# SCH_Radio.net
KiCad netlist of a schematic drawn in Altium Designer
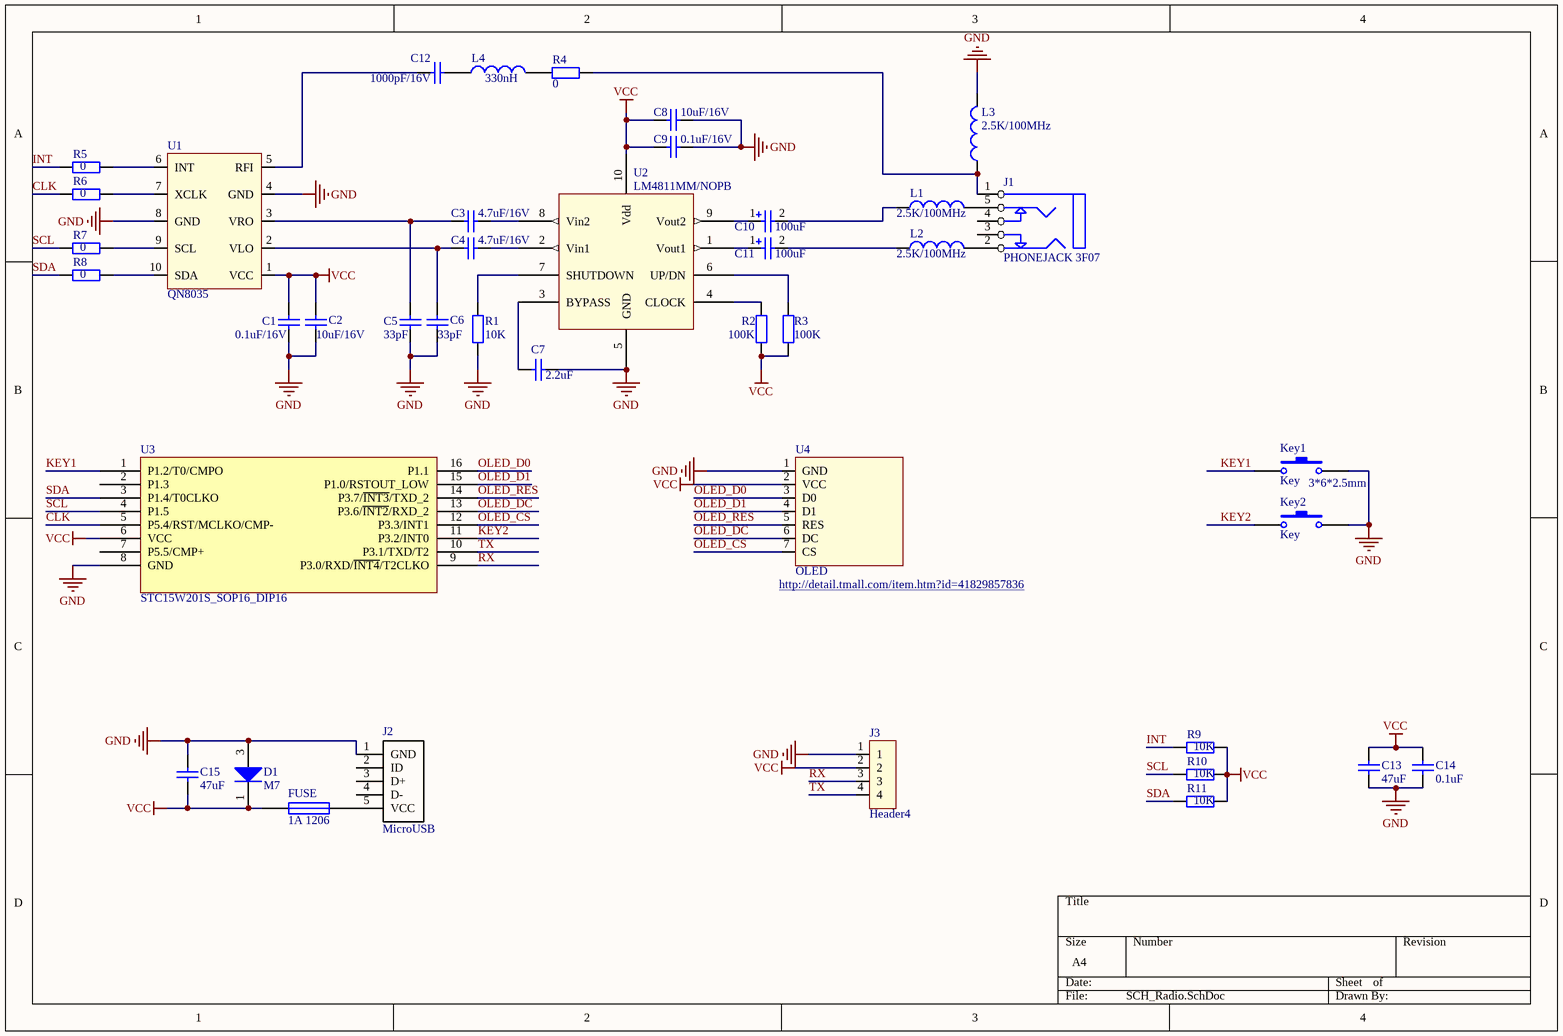
[diagram p0: SCH_Radio.SchDoc]

(export (version "E")
  (design (tool "Eeschema 10.0.6"))
  (components
    (comp (ref "C1")
      (value "0.1uF/16V")
      (footprint "0603")
      (description "Capacitor")
      (fields (field (name "Comment") "Cap") (field (name "PUBLISHER") "Altium Limited"))
      (libsource (lib "Miscellaneous Devices") (part "Cap"))
    )
    (comp (ref "C2")
      (value "10uF/16V")
      (footprint "0805")
      (description "Capacitor")
      (fields (field (name "Comment") "Cap") (field (name "PUBLISHER") "Altium Limited"))
      (libsource (lib "Miscellaneous Devices") (part "Cap"))
    )
    (comp (ref "C3")
      (value "4.7uF/16V")
      (footprint "0603")
      (description "Capacitor")
      (fields (field (name "Comment") "Cap") (field (name "PUBLISHER") "Altium Limited"))
      (libsource (lib "Miscellaneous Devices") (part "Cap"))
    )
    (comp (ref "C4")
      (value "4.7uF/16V")
      (footprint "0603")
      (description "Capacitor")
      (fields (field (name "Comment") "Cap") (field (name "PUBLISHER") "Altium Limited"))
      (libsource (lib "Miscellaneous Devices") (part "Cap"))
    )
    (comp (ref "C5")
      (value "33pF")
      (footprint "0603")
      (description "Capacitor")
      (fields (field (name "Comment") "Cap") (field (name "PUBLISHER") "Altium Limited"))
      (libsource (lib "Miscellaneous Devices") (part "Cap"))
    )
    (comp (ref "C6")
      (value "33pF")
      (footprint "0603")
      (description "Capacitor")
      (fields (field (name "Comment") "Cap") (field (name "PUBLISHER") "Altium Limited"))
      (libsource (lib "Miscellaneous Devices") (part "Cap"))
    )
    (comp (ref "C7")
      (value "2.2uF")
      (footprint "0603")
      (description "Capacitor")
      (fields (field (name "Comment") "Cap") (field (name "PUBLISHER") "Altium Limited"))
      (libsource (lib "Miscellaneous Devices") (part "Cap"))
    )
    (comp (ref "C8")
      (value "10uF/16V")
      (footprint "0805")
      (description "Capacitor")
      (fields (field (name "Comment") "Cap") (field (name "PUBLISHER") "Altium Limited"))
      (libsource (lib "Miscellaneous Devices") (part "Cap"))
    )
    (comp (ref "C9")
      (value "0.1uF/16V")
      (footprint "0603")
      (description "Capacitor")
      (fields (field (name "Comment") "Cap") (field (name "PUBLISHER") "Altium Limited"))
      (libsource (lib "Miscellaneous Devices") (part "Cap"))
    )
    (comp (ref "C10")
      (value "100uF")
      (footprint "6032")
      (description "Polarized Capacitor (Axial)")
      (fields (field (name "Comment") "Cap Pol2") (field (name "PUBLISHER") "Altium Limited"))
      (libsource (lib "Miscellaneous Devices") (part "Cap Pol2"))
    )
    (comp (ref "C11")
      (value "100uF")
      (footprint "6032")
      (description "Polarized Capacitor (Axial)")
      (fields (field (name "Comment") "Cap Pol2") (field (name "PUBLISHER") "Altium Limited"))
      (libsource (lib "Miscellaneous Devices") (part "Cap Pol2"))
    )
    (comp (ref "C12")
      (value "1000pF/16V")
      (footprint "0603")
      (description "Capacitor")
      (fields (field (name "Comment") "Cap") (field (name "PUBLISHER") "Altium Limited"))
      (libsource (lib "Miscellaneous Devices") (part "Cap"))
    )
    (comp (ref "C13")
      (value "47uF")
      (footprint "0805")
      (description "Capacitor")
      (fields (field (name "Comment") "Cap") (field (name "PUBLISHER") "Altium Limited"))
      (libsource (lib "Miscellaneous Devices") (part "Cap"))
    )
    (comp (ref "C14")
      (value "0.1uF")
      (footprint "0603")
      (description "Capacitor")
      (fields (field (name "Comment") "Cap") (field (name "PUBLISHER") "Altium Limited"))
      (libsource (lib "Miscellaneous Devices") (part "Cap"))
    )
    (comp (ref "C15")
      (value "47uF")
      (footprint "0805")
      (description "Capacitor")
      (fields (field (name "Comment") "Cap") (field (name "PUBLISHER") "Altium Limited"))
      (libsource (lib "Miscellaneous Devices") (part "Cap"))
    )
    (comp (ref "D1")
      (value "M7")
      (footprint "DO-214AC")
      (description "Default Diode")
      (fields (field (name "PUBLISHER") "Altium Limited"))
      (libsource (lib "Miscellaneous Devices") (part "Diode"))
    )
    (comp (ref "FUSE")
      (value "1A 1206")
      (footprint "1206")
      (description "Fuse")
      (fields (field (name "PUBLISHER") "Altium Limited"))
      (libsource (lib "Miscellaneous Devices") (part "Fuse 1"))
    )
    (comp (ref "J1")
      (value "PHONEJACK 3F07")
      (footprint "3F07")
      (libsource (lib "SCH_Library") (part "PHONEJACK STEREO SW"))
    )
    (comp (ref "J2")
      (value "MicroUSB")
      (footprint "MicroUSB")
      (description "Imported")
      (libsource (lib "SCH_Library") (part "MicroUSB"))
    )
    (comp (ref "J3") (value "Header4") (footprint "HEADER4") (libsource (lib "SCH_Library") (part "Header4")))
    (comp (ref "Key1")
      (value "Key")
      (footprint "key")
      (fields (field (name "G") "3*6*2.5mm"))
      (libsource (lib "SCH_Library") (part "Key"))
    )
    (comp (ref "Key2") (value "Key") (footprint "key") (libsource (lib "SCH_Library") (part "Key")))
    (comp (ref "L1")
      (value "2.5K/100MHz")
      (footprint "0603")
      (description "Inductor")
      (fields (field (name "PUBLISHER") "Altium Limited"))
      (libsource (lib "Miscellaneous Devices") (part "Inductor"))
    )
    (comp (ref "L2")
      (value "2.5K/100MHz")
      (footprint "0603")
      (description "Inductor")
      (fields (field (name "PUBLISHER") "Altium Limited"))
      (libsource (lib "Miscellaneous Devices") (part "Inductor"))
    )
    (comp (ref "L3")
      (value "2.5K/100MHz")
      (footprint "0603")
      (description "Inductor")
      (fields (field (name "PUBLISHER") "Altium Limited"))
      (libsource (lib "Miscellaneous Devices") (part "Inductor"))
    )
    (comp (ref "L4")
      (value "330nH")
      (footprint "0603")
      (description "Inductor")
      (fields (field (name "PUBLISHER") "Altium Limited"))
      (libsource (lib "Miscellaneous Devices") (part "Inductor"))
    )
    (comp (ref "R1")
      (value "10K")
      (footprint "0603")
      (description "Resistor")
      (fields (field (name "Comment") "Res2") (field (name "PUBLISHER") "Altium Limited"))
      (libsource (lib "Miscellaneous Devices") (part "Res2"))
    )
    (comp (ref "R2")
      (value "100K")
      (footprint "0603")
      (description "Resistor")
      (fields (field (name "Comment") "Res2") (field (name "PUBLISHER") "Altium Limited"))
      (libsource (lib "Miscellaneous Devices") (part "Res2"))
    )
    (comp (ref "R3")
      (value "100K")
      (footprint "0603")
      (description "Resistor")
      (fields (field (name "Comment") "Res2") (field (name "PUBLISHER") "Altium Limited"))
      (libsource (lib "Miscellaneous Devices") (part "Res2"))
    )
    (comp (ref "R4")
      (value "0")
      (footprint "0603")
      (description "Resistor")
      (fields (field (name "Comment") "Res2") (field (name "PUBLISHER") "Altium Limited"))
      (libsource (lib "") (part "Res2_1"))
    )
    (comp (ref "R5")
      (value "0")
      (footprint "0603")
      (description "Resistor")
      (fields (field (name "Comment") "Res2") (field (name "PUBLISHER") "Altium Limited"))
      (libsource (lib "") (part "Res2_1"))
    )
    (comp (ref "R6")
      (value "0")
      (footprint "0603")
      (description "Resistor")
      (fields (field (name "Comment") "Res2") (field (name "PUBLISHER") "Altium Limited"))
      (libsource (lib "") (part "Res2_1"))
    )
    (comp (ref "R7")
      (value "0")
      (footprint "0603")
      (description "Resistor")
      (fields (field (name "Comment") "Res2") (field (name "PUBLISHER") "Altium Limited"))
      (libsource (lib "") (part "Res2_1"))
    )
    (comp (ref "R8")
      (value "0")
      (footprint "0603")
      (description "Resistor")
      (fields (field (name "Comment") "Res2") (field (name "PUBLISHER") "Altium Limited"))
      (libsource (lib "") (part "Res2_1"))
    )
    (comp (ref "R9")
      (value "10K")
      (footprint "0603")
      (description "Resistor")
      (fields (field (name "Comment") "Res2") (field (name "PUBLISHER") "Altium Limited"))
      (libsource (lib "") (part "Res2_1"))
    )
    (comp (ref "R10")
      (value "10K")
      (footprint "0603")
      (description "Resistor")
      (fields (field (name "Comment") "Res2") (field (name "PUBLISHER") "Altium Limited"))
      (libsource (lib "") (part "Res2_1"))
    )
    (comp (ref "R11")
      (value "10K")
      (footprint "0603")
      (description "Resistor")
      (fields (field (name "Comment") "Res2") (field (name "PUBLISHER") "Altium Limited"))
      (libsource (lib "") (part "Res2_1"))
    )
    (comp (ref "U1") (value "QN8035") (footprint "SOP10") (libsource (lib "SCH_Library") (part "QN8035")))
    (comp (ref "U2")
      (value "LM4811MM/NOPB")
      (footprint "MUB10Am")
      (description "Imported")
      (fields (field (name "RS PART NUMBER") "5359802"))
      (libsource (lib "SCH_Library") (part "LM4811MM/NOPB"))
    )
    (comp (ref "U3")
      (value "STC15W201S_SOP16_DIP16")
      (footprint "SOP16")
      (libsource (lib "SCH_Library") (part "STC15W201S_SOP16_DIP16"))
    )
    (comp (ref "U4")
      (value "OLED")
      (footprint "OLED_0.96")
      (fields (field (name "URL") "http://detail.tmall.com/item.htm?id=41829857836"))
      (libsource (lib "SCH_Library") (part "OLED"))
    )
  )
  (nets
    (net (code "1") (name "/CLK") (class "Default")
      (node (ref "R6") (pin "2") (pinfunction "2_2") (pintype "passive"))
      (node (ref "U3") (pin "5") (pinfunction "P5.4/RST/MCLKO/CMP-_5") (pintype "passive"))
    )
    (net (code "2") (name "/INT") (class "Default")
      (node (ref "R5") (pin "2") (pinfunction "2_2") (pintype "passive"))
      (node (ref "R9") (pin "2") (pinfunction "2_2") (pintype "passive"))
    )
    (net (code "3") (name "/KEY1") (class "Default")
      (node (ref "Key1") (pin "1") (pinfunction "1_1") (pintype "passive"))
      (node (ref "U3") (pin "1") (pinfunction "P1.2/T0/CMPO_1") (pintype "passive"))
    )
    (net (code "4") (name "/KEY2") (class "Default")
      (node (ref "Key2") (pin "1") (pinfunction "1_1") (pintype "passive"))
      (node (ref "U3") (pin "11") (pinfunction "P3.2/INT0_11") (pintype "passive"))
    )
    (net (code "5") (name "/OLED_CS") (class "Default")
      (node (ref "U3") (pin "12") (pinfunction "P3.3/INT1_12") (pintype "passive"))
      (node (ref "U4") (pin "7") (pinfunction "CS_7") (pintype "passive"))
    )
    (net (code "6") (name "/OLED_D0") (class "Default")
      (node (ref "U3") (pin "16") (pinfunction "P1.1_16") (pintype "passive"))
      (node (ref "U4") (pin "3") (pinfunction "D0_3") (pintype "passive"))
    )
    (net (code "7") (name "/OLED_D1") (class "Default")
      (node (ref "U3") (pin "15") (pinfunction "P1.0/RSTOUT_LOW_15") (pintype "passive"))
      (node (ref "U4") (pin "4") (pinfunction "D1_4") (pintype "passive"))
    )
    (net (code "8") (name "/OLED_DC") (class "Default")
      (node (ref "U3") (pin "13") (pinfunction "P3.6/~{INT2}/RXD_2_13") (pintype "passive"))
      (node (ref "U4") (pin "6") (pinfunction "DC_6") (pintype "passive"))
    )
    (net (code "9") (name "/OLED_RES") (class "Default")
      (node (ref "U3") (pin "14") (pinfunction "P3.7/~{INT3}/TXD_2_14") (pintype "passive"))
      (node (ref "U4") (pin "5") (pinfunction "RES_5") (pintype "passive"))
    )
    (net (code "10") (name "/RX") (class "Default")
      (node (ref "J3") (pin "3") (pinfunction "3_3") (pintype "passive"))
      (node (ref "U3") (pin "9") (pinfunction "P3.0/RXD/~{INT4}/T2CLKO_9") (pintype "passive"))
    )
    (net (code "11") (name "/SCL") (class "Default")
      (node (ref "R10") (pin "2") (pinfunction "2_2") (pintype "passive"))
      (node (ref "R7") (pin "2") (pinfunction "2_2") (pintype "passive"))
      (node (ref "U3") (pin "4") (pinfunction "P1.5_4") (pintype "passive"))
    )
    (net (code "12") (name "/SDA") (class "Default")
      (node (ref "R11") (pin "2") (pinfunction "2_2") (pintype "passive"))
      (node (ref "R8") (pin "2") (pinfunction "2_2") (pintype "passive"))
      (node (ref "U3") (pin "3") (pinfunction "P1.4/T0CLKO_3") (pintype "passive"))
    )
    (net (code "13") (name "/TX") (class "Default")
      (node (ref "J3") (pin "4") (pinfunction "4_4") (pintype "passive"))
      (node (ref "U3") (pin "10") (pinfunction "P3.1/TXD/T2_10") (pintype "passive"))
    )
    (net (code "14") (name "GND") (class "Default")
      (node (ref "C1") (pin "1") (pinfunction "1_1") (pintype "passive"))
      (node (ref "C13") (pin "2") (pinfunction "2_2") (pintype "passive"))
      (node (ref "C14") (pin "2") (pinfunction "2_2") (pintype "passive"))
      (node (ref "C15") (pin "1") (pinfunction "1_1") (pintype "passive"))
      (node (ref "C2") (pin "1") (pinfunction "1_1") (pintype "passive"))
      (node (ref "C5") (pin "1") (pinfunction "1_1") (pintype "passive"))
      (node (ref "C6") (pin "1") (pinfunction "1_1") (pintype "passive"))
      (node (ref "C7") (pin "2") (pinfunction "2_2") (pintype "passive"))
      (node (ref "C8") (pin "2") (pinfunction "2_2") (pintype "passive"))
      (node (ref "C9") (pin "2") (pinfunction "2_2") (pintype "passive"))
      (node (ref "D1") (pin "3") (pinfunction "A_3") (pintype "passive"))
      (node (ref "J2") (pin "1") (pinfunction "GND_1") (pintype "passive"))
      (node (ref "J3") (pin "1") (pinfunction "1_1") (pintype "passive"))
      (node (ref "Key1") (pin "2") (pinfunction "2_2") (pintype "passive"))
      (node (ref "Key2") (pin "2") (pinfunction "2_2") (pintype "passive"))
      (node (ref "L3") (pin "2") (pinfunction "2_2") (pintype "passive"))
      (node (ref "R1") (pin "1") (pinfunction "1_1") (pintype "passive"))
      (node (ref "U1") (pin "4") (pinfunction "GND_4") (pintype "passive"))
      (node (ref "U1") (pin "8") (pinfunction "GND_8") (pintype "passive"))
      (node (ref "U2") (pin "5") (pinfunction "GND_5") (pintype "passive"))
      (node (ref "U3") (pin "8") (pinfunction "GND_8") (pintype "passive"))
      (node (ref "U4") (pin "1") (pinfunction "GND_1") (pintype "passive"))
    )
    (net (code "15") (name "Net-(C10-Pad2)") (class "Default")
      (node (ref "C10") (pin "2") (pinfunction "2_2") (pintype "passive"))
      (node (ref "L1") (pin "1") (pinfunction "1_1") (pintype "passive"))
    )
    (net (code "16") (name "Net-(C11-Pad2)") (class "Default")
      (node (ref "C11") (pin "2") (pinfunction "2_2") (pintype "passive"))
      (node (ref "L2") (pin "1") (pinfunction "1_1") (pintype "passive"))
    )
    (net (code "17") (name "Net-(C12-Pad1)") (class "Default")
      (node (ref "C12") (pin "1") (pinfunction "1_1") (pintype "passive"))
      (node (ref "L4") (pin "1") (pinfunction "1_1") (pintype "passive"))
    )
    (net (code "18") (name "Net-(J1-A)") (class "Default")
      (node (ref "J1") (pin "2") (pinfunction "A_2") (pintype "passive"))
      (node (ref "L2") (pin "2") (pinfunction "2_2") (pintype "passive"))
    )
    (net (code "19") (name "Net-(J1-D)") (class "Default")
      (node (ref "J1") (pin "5") (pinfunction "D_5") (pintype "passive"))
      (node (ref "L1") (pin "2") (pinfunction "2_2") (pintype "passive"))
    )
    (net (code "20") (name "Net-(J1-E)") (class "Default")
      (node (ref "J1") (pin "1") (pinfunction "E_1") (pintype "passive"))
      (node (ref "L3") (pin "1") (pinfunction "1_1") (pintype "passive"))
      (node (ref "R4") (pin "1") (pinfunction "1_1") (pintype "passive"))
    )
    (net (code "21") (name "Net-(J2-VCC)") (class "Default")
      (node (ref "FUSE") (pin "2") (pinfunction "2_2") (pintype "passive"))
      (node (ref "J2") (pin "5") (pinfunction "VCC_5") (pintype "passive"))
    )
    (net (code "22") (name "Net-(L4-Pad2)") (class "Default")
      (node (ref "L4") (pin "2") (pinfunction "2_2") (pintype "passive"))
      (node (ref "R4") (pin "2") (pinfunction "2_2") (pintype "passive"))
    )
    (net (code "23") (name "Net-(U1-INT)") (class "Default")
      (node (ref "R5") (pin "1") (pinfunction "1_1") (pintype "passive"))
      (node (ref "U1") (pin "6") (pinfunction "INT_6") (pintype "passive"))
    )
    (net (code "24") (name "Net-(U1-RFI)") (class "Default")
      (node (ref "C12") (pin "2") (pinfunction "2_2") (pintype "passive"))
      (node (ref "U1") (pin "5") (pinfunction "RFI_5") (pintype "passive"))
    )
    (net (code "25") (name "Net-(U1-SCL)") (class "Default")
      (node (ref "R7") (pin "1") (pinfunction "1_1") (pintype "passive"))
      (node (ref "U1") (pin "9") (pinfunction "SCL_9") (pintype "passive"))
    )
    (net (code "26") (name "Net-(U1-SDA)") (class "Default")
      (node (ref "R8") (pin "1") (pinfunction "1_1") (pintype "passive"))
      (node (ref "U1") (pin "10") (pinfunction "SDA_10") (pintype "passive"))
    )
    (net (code "27") (name "Net-(U1-VLO)") (class "Default")
      (node (ref "C4") (pin "1") (pinfunction "1_1") (pintype "passive"))
      (node (ref "C6") (pin "2") (pinfunction "2_2") (pintype "passive"))
      (node (ref "U1") (pin "2") (pinfunction "VLO_2") (pintype "passive"))
    )
    (net (code "28") (name "Net-(U1-VRO)") (class "Default")
      (node (ref "C3") (pin "1") (pinfunction "1_1") (pintype "passive"))
      (node (ref "C5") (pin "2") (pinfunction "2_2") (pintype "passive"))
      (node (ref "U1") (pin "3") (pinfunction "VRO_3") (pintype "passive"))
    )
    (net (code "29") (name "Net-(U1-XCLK)") (class "Default")
      (node (ref "R6") (pin "1") (pinfunction "1_1") (pintype "passive"))
      (node (ref "U1") (pin "7") (pinfunction "XCLK_7") (pintype "passive"))
    )
    (net (code "30") (name "Net-(U2-BYPASS)") (class "Default")
      (node (ref "C7") (pin "1") (pinfunction "1_1") (pintype "passive"))
      (node (ref "U2") (pin "3") (pinfunction "BYPASS_3") (pintype "passive"))
    )
    (net (code "31") (name "Net-(U2-CLOCK)") (class "Default")
      (node (ref "R2") (pin "2") (pinfunction "2_2") (pintype "passive"))
      (node (ref "U2") (pin "4") (pinfunction "CLOCK_4") (pintype "passive"))
    )
    (net (code "32") (name "Net-(U2-SHUTDOWN)") (class "Default")
      (node (ref "R1") (pin "2") (pinfunction "2_2") (pintype "passive"))
      (node (ref "U2") (pin "7") (pinfunction "SHUTDOWN_7") (pintype "passive"))
    )
    (net (code "33") (name "Net-(U2-UP{slash}DN)") (class "Default")
      (node (ref "R3") (pin "2") (pinfunction "2_2") (pintype "passive"))
      (node (ref "U2") (pin "6") (pinfunction "UP/DN_6") (pintype "passive"))
    )
    (net (code "34") (name "Net-(U2-Vin1)") (class "Default")
      (node (ref "C4") (pin "2") (pinfunction "2_2") (pintype "passive"))
      (node (ref "U2") (pin "2") (pinfunction "Vin1_2") (pintype "output"))
    )
    (net (code "35") (name "Net-(U2-Vin2)") (class "Default")
      (node (ref "C3") (pin "2") (pinfunction "2_2") (pintype "passive"))
      (node (ref "U2") (pin "8") (pinfunction "Vin2_8") (pintype "output"))
    )
    (net (code "36") (name "Net-(U2-Vout1)") (class "Default")
      (node (ref "C11") (pin "1") (pinfunction "1_1") (pintype "passive"))
      (node (ref "U2") (pin "1") (pinfunction "Vout1_1") (pintype "output"))
    )
    (net (code "37") (name "Net-(U2-Vout2)") (class "Default")
      (node (ref "C10") (pin "1") (pinfunction "1_1") (pintype "passive"))
      (node (ref "U2") (pin "9") (pinfunction "Vout2_9") (pintype "output"))
    )
    (net (code "38") (name "VCC") (class "Default")
      (node (ref "C1") (pin "2") (pinfunction "2_2") (pintype "passive"))
      (node (ref "C13") (pin "1") (pinfunction "1_1") (pintype "passive"))
      (node (ref "C14") (pin "1") (pinfunction "1_1") (pintype "passive"))
      (node (ref "C15") (pin "2") (pinfunction "2_2") (pintype "passive"))
      (node (ref "C2") (pin "2") (pinfunction "2_2") (pintype "passive"))
      (node (ref "C8") (pin "1") (pinfunction "1_1") (pintype "passive"))
      (node (ref "C9") (pin "1") (pinfunction "1_1") (pintype "passive"))
      (node (ref "D1") (pin "1") (pinfunction "K_1") (pintype "passive"))
      (node (ref "FUSE") (pin "1") (pinfunction "1_1") (pintype "passive"))
      (node (ref "J3") (pin "2") (pinfunction "2_2") (pintype "passive"))
      (node (ref "R10") (pin "1") (pinfunction "1_1") (pintype "passive"))
      (node (ref "R11") (pin "1") (pinfunction "1_1") (pintype "passive"))
      (node (ref "R2") (pin "1") (pinfunction "1_1") (pintype "passive"))
      (node (ref "R3") (pin "1") (pinfunction "1_1") (pintype "passive"))
      (node (ref "R9") (pin "1") (pinfunction "1_1") (pintype "passive"))
      (node (ref "U1") (pin "1") (pinfunction "VCC_1") (pintype "passive"))
      (node (ref "U2") (pin "10") (pinfunction "Vdd_10") (pintype "passive"))
      (node (ref "U3") (pin "6") (pinfunction "VCC_6") (pintype "passive"))
      (node (ref "U4") (pin "2") (pinfunction "VCC_2") (pintype "passive"))
    )
    (net (code "39") (name "unconnected-(J1-B-Pad3)") (class "Default")
      (node (ref "J1") (pin "3") (pinfunction "B_3") (pintype "passive"))
    )
    (net (code "40") (name "unconnected-(J1-C-Pad4)") (class "Default")
      (node (ref "J1") (pin "4") (pinfunction "C_4") (pintype "passive"))
    )
    (net (code "41") (name "unconnected-(J2-D+-Pad3)") (class "Default")
      (node (ref "J2") (pin "3") (pinfunction "D+_3") (pintype "passive"))
    )
    (net (code "42") (name "unconnected-(J2-D--Pad4)") (class "Default")
      (node (ref "J2") (pin "4") (pinfunction "D-_4") (pintype "passive"))
    )
    (net (code "43") (name "unconnected-(J2-ID-Pad2)") (class "Default")
      (node (ref "J2") (pin "2") (pinfunction "ID_2") (pintype "passive"))
    )
    (net (code "44") (name "unconnected-(U3-P1.3-Pad2)") (class "Default")
      (node (ref "U3") (pin "2") (pinfunction "P1.3_2") (pintype "passive"))
    )
    (net (code "45") (name "unconnected-(U3-P5.5{slash}CMP+-Pad7)") (class "Default")
      (node (ref "U3") (pin "7") (pinfunction "P5.5/CMP+_7") (pintype "passive"))
    )
  )
)
